# SPS_V2-5.net
KiCad netlist of a schematic drawn in EAGLE
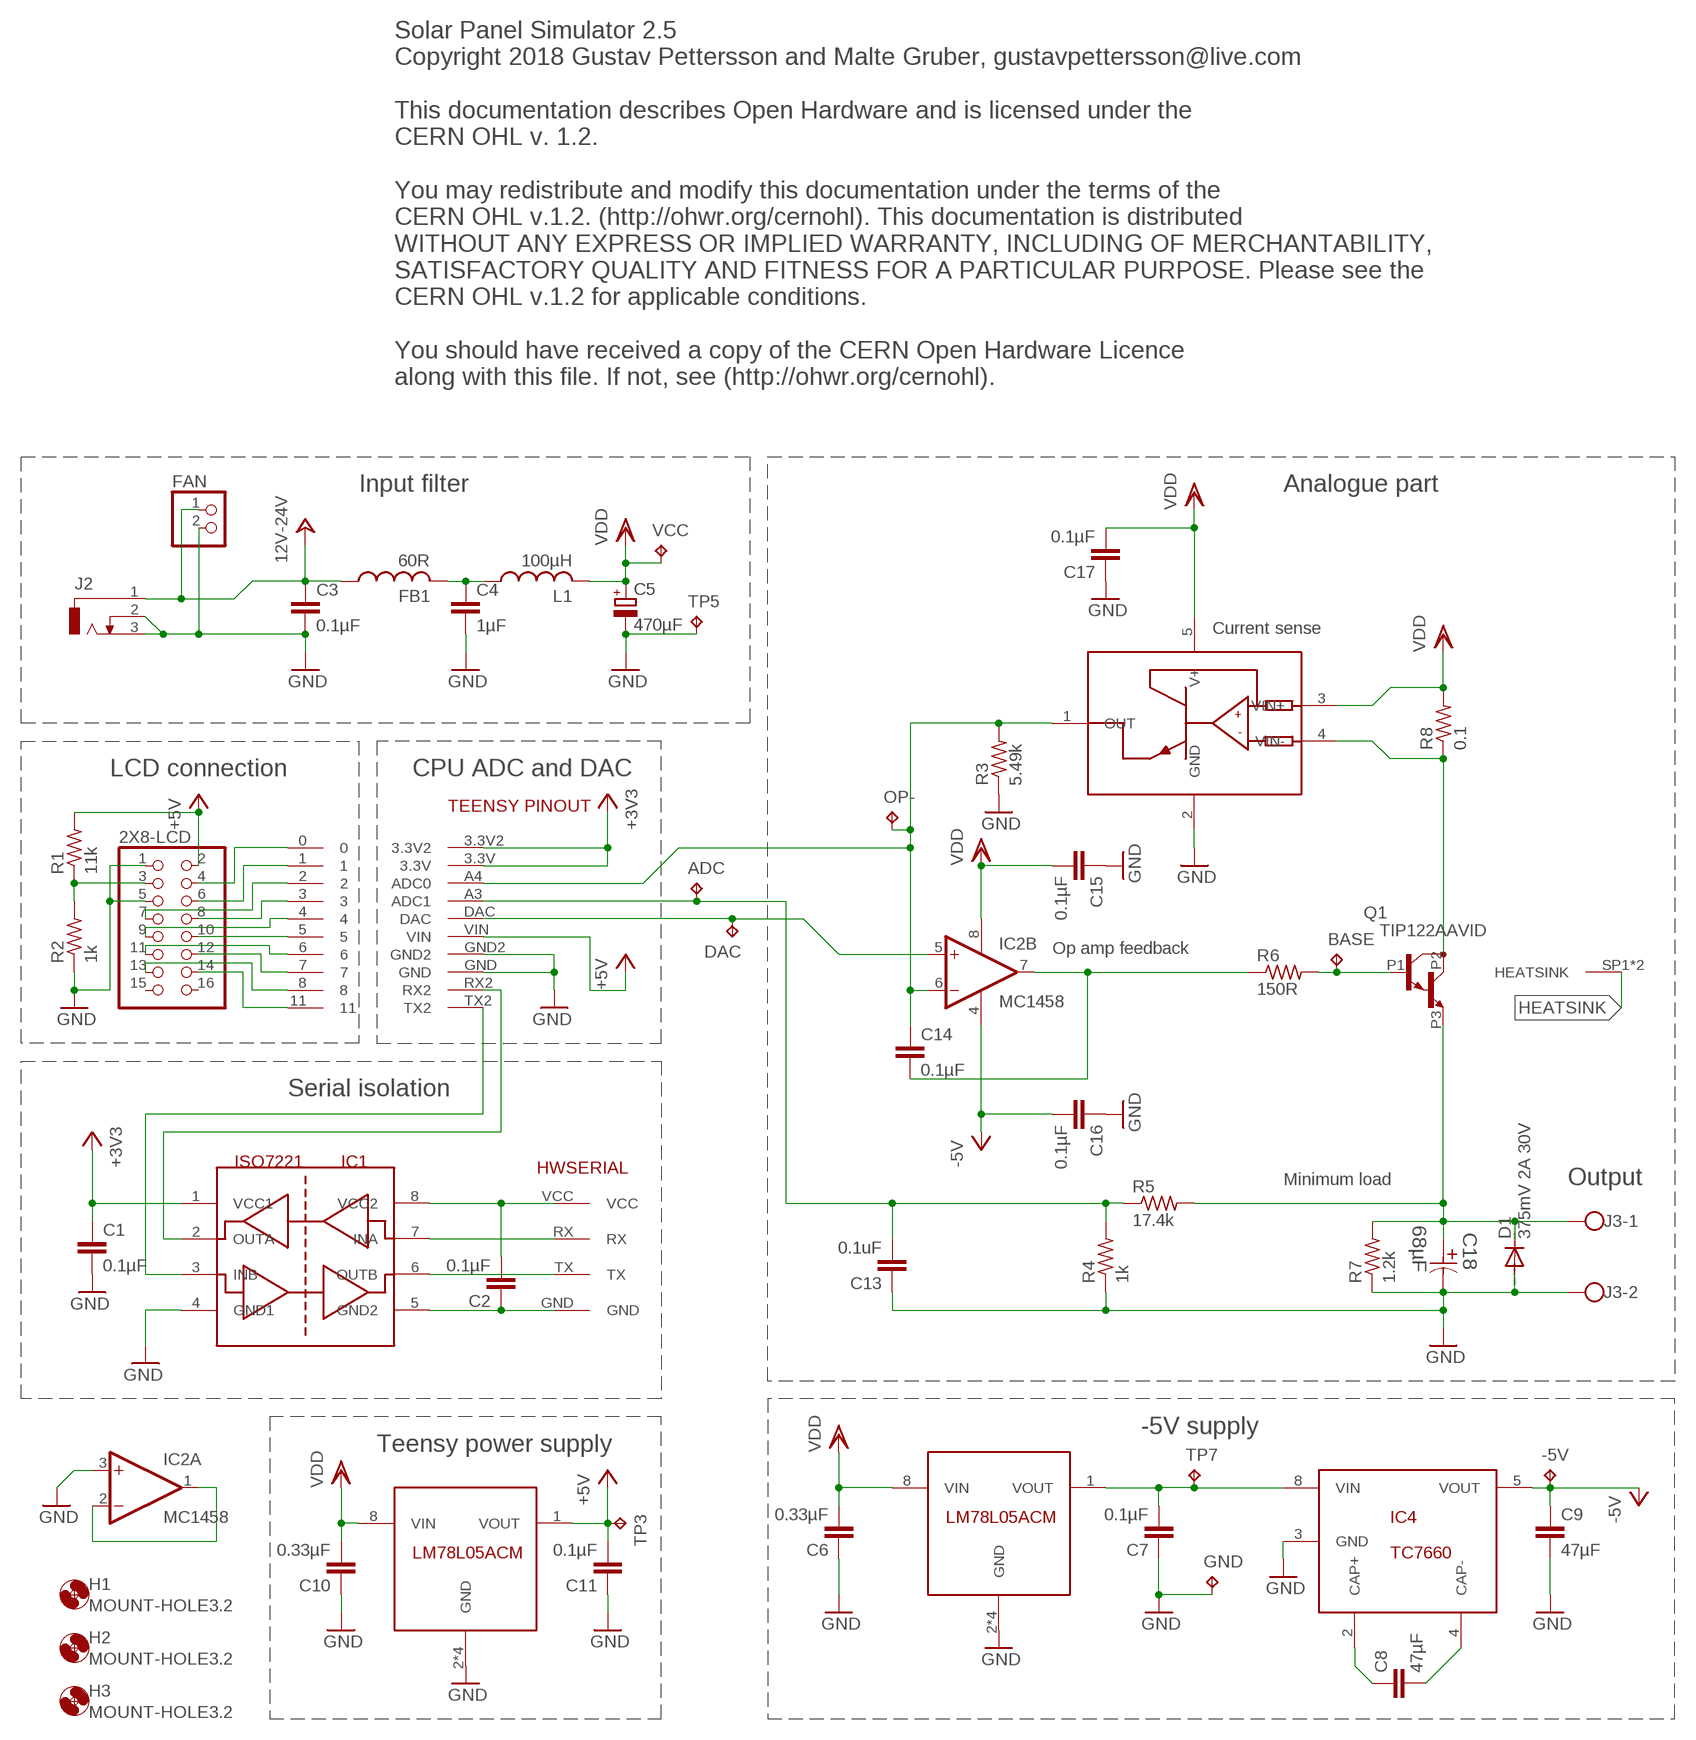
[diagram p0: schematic, sheet 1]

(export (version "E")
  (design (tool "Eeschema 10.0.6"))
  (components
    (comp (ref "-5V")
      (value "TPTP10R")
      (footprint "eagle-import:TP10R")
      (libsource (lib "eagle-import") (part "TPTP10R"))
    )
    (comp (ref "2X8-LCD")
      (value "PINHD-2X8")
      (footprint "eagle-import:2X08")
      (libsource (lib "eagle-import") (part "PINHD-2X8"))
    )
    (comp (ref "ADC")
      (value "TPTP10R")
      (footprint "eagle-import:TP10R")
      (libsource (lib "eagle-import") (part "TPTP10R"))
    )
    (comp (ref "BASE")
      (value "TPTP10R")
      (footprint "eagle-import:TP10R")
      (libsource (lib "eagle-import") (part "TPTP10R"))
    )
    (comp (ref "C1")
      (value "0.1µF")
      (footprint "eagle-import:C0603")
      (libsource (lib "eagle-import") (part "C-EUC0603"))
    )
    (comp (ref "C2")
      (value "0.1µF")
      (footprint "eagle-import:C0603")
      (libsource (lib "eagle-import") (part "C-EUC0603"))
    )
    (comp (ref "C3")
      (value "0.1µF")
      (footprint "eagle-import:C0603")
      (libsource (lib "eagle-import") (part "C-EUC0603"))
    )
    (comp (ref "C4")
      (value "1µF")
      (footprint "eagle-import:C0603")
      (libsource (lib "eagle-import") (part "C-EUC0603"))
    )
    (comp (ref "C5")
      (value "470µF")
      (footprint "eagle-import:12.5MMSMD")
      (libsource (lib "eagle-import") (part "12.5CAP"))
    )
    (comp (ref "C6")
      (value "0.33µF")
      (footprint "eagle-import:C0603")
      (libsource (lib "eagle-import") (part "C-EUC0603"))
    )
    (comp (ref "C7")
      (value "0.1µF")
      (footprint "eagle-import:C0603")
      (libsource (lib "eagle-import") (part "C-EUC0603"))
    )
    (comp (ref "C8")
      (value "47µF")
      (footprint "eagle-import:C1206")
      (libsource (lib "eagle-import") (part "resistor_C-EUC1206"))
    )
    (comp (ref "C9")
      (value "47µF")
      (footprint "eagle-import:C1206")
      (libsource (lib "eagle-import") (part "resistor_C-EUC1206"))
    )
    (comp (ref "C10")
      (value "0.33µF")
      (footprint "eagle-import:C0603")
      (libsource (lib "eagle-import") (part "C-EUC0603"))
    )
    (comp (ref "C11")
      (value "0.1µF")
      (footprint "eagle-import:C0603")
      (libsource (lib "eagle-import") (part "C-EUC0603"))
    )
    (comp (ref "C13")
      (value "0.1uF")
      (footprint "eagle-import:C0603")
      (libsource (lib "eagle-import") (part "C-EUC0603"))
    )
    (comp (ref "C14")
      (value "0.1µF")
      (footprint "eagle-import:C0603")
      (libsource (lib "eagle-import") (part "C-EUC0603"))
    )
    (comp (ref "C15")
      (value "0.1µF")
      (footprint "eagle-import:C0603")
      (libsource (lib "eagle-import") (part "C-EUC0603"))
    )
    (comp (ref "C16")
      (value "0.1µF")
      (footprint "eagle-import:C0603")
      (libsource (lib "eagle-import") (part "C-EUC0603"))
    )
    (comp (ref "C17")
      (value "0.1µF")
      (footprint "eagle-import:C0603")
      (libsource (lib "eagle-import") (part "C-EUC0603"))
    )
    (comp (ref "C18")
      (value "68µF")
      (footprint "eagle-import:CAPAE660X800N")
      (fields (field (name "MPN") "EEE-FPV680XAP") (field (name "TOLERANCE") "±20 %"))
      (libsource (lib "eagle-import") (part "EEE--CASE-D8FPV680XAP"))
    )
    (comp (ref "D1")
      (value "375mV 2A 30V")
      (footprint "eagle-import:DO214AC")
      (libsource (lib "eagle-import") (part "DIODE-DO214AC"))
    )
    (comp (ref "DAC")
      (value "TPTP10R")
      (footprint "eagle-import:TP10R")
      (libsource (lib "eagle-import") (part "TPTP10R"))
    )
    (comp (ref "DB1")
      (value "TEENSY3.2")
      (footprint "eagle-import:TEENSY3.2")
      (libsource (lib "eagle-import") (part "TEENSY3.2"))
    )
    (comp (ref "FAN")
      (value "PINHD-1X2")
      (footprint "eagle-import:1X02")
      (libsource (lib "eagle-import") (part "PINHD-1X2"))
    )
    (comp (ref "FB1")
      (value "60R")
      (footprint "eagle-import:R1206")
      (libsource (lib "eagle-import") (part "1206FERRITEBEAD"))
    )
    (comp (ref "GND")
      (value "TPTP10R")
      (footprint "eagle-import:TP10R")
      (libsource (lib "eagle-import") (part "TPTP10R"))
    )
    (comp (ref "H1")
      (value "MOUNT-HOLE3.2")
      (footprint "eagle-import:3,2")
      (libsource (lib "eagle-import") (part "MOUNT-HOLE3.2"))
    )
    (comp (ref "H2")
      (value "MOUNT-HOLE3.2")
      (footprint "eagle-import:3,2")
      (libsource (lib "eagle-import") (part "MOUNT-HOLE3.2"))
    )
    (comp (ref "H3")
      (value "MOUNT-HOLE3.2")
      (footprint "eagle-import:3,2")
      (libsource (lib "eagle-import") (part "MOUNT-HOLE3.2"))
    )
    (comp (ref "IC1")
      (value "ISO7221")
      (footprint "eagle-import:SO8")
      (libsource (lib "eagle-import") (part "ISO7221"))
    )
    (comp (ref "IC2")
      (value "MC1458")
      (footprint "eagle-import:SO08")
      (libsource (lib "eagle-import") (part "4558DLM"))
    )
    (comp (ref "IC3")
      (value "LM78L05ACM")
      (footprint "eagle-import:SO8")
      (libsource (lib "eagle-import") (part "LM78L05ACM"))
    )
    (comp (ref "IC4")
      (value "TC7660")
      (footprint "eagle-import:SO8")
      (libsource (lib "eagle-import") (part "TL7660"))
    )
    (comp (ref "IC5")
      (value "LM78L05ACM")
      (footprint "eagle-import:SO8")
      (libsource (lib "eagle-import") (part "LM78L05ACM"))
    )
    (comp (ref "IC6")
      (value "INA139")
      (footprint "eagle-import:SOT23-5L")
      (libsource (lib "eagle-import") (part "INA139"))
    )
    (comp (ref "J1")
      (value "HWSERIAL")
      (footprint "eagle-import:HWSERIAL")
      (libsource (lib "eagle-import") (part "HWSERIAL"))
    )
    (comp (ref "J2")
      (value "DCJ0303")
      (footprint "eagle-import:DCJ0303")
      (libsource (lib "eagle-import") (part "DCJ0303"))
    )
    (comp (ref "J3")
      (value "W237-102")
      (footprint "eagle-import:W237-102")
      (fields (field (name "MPN") "237-102"))
      (libsource (lib "eagle-import") (part "W237-102"))
    )
    (comp (ref "L1")
      (value "100µH")
      (footprint "eagle-import:1210INDUCTOR")
      (libsource (lib "eagle-import") (part "1210INDUCTOR"))
    )
    (comp (ref "OP-")
      (value "TPTP10R")
      (footprint "eagle-import:TP10R")
      (libsource (lib "eagle-import") (part "TPTP10R"))
    )
    (comp (ref "Q1")
      (value "TIP122AAVID")
      (footprint "eagle-import:OP-220-AAVID")
      (libsource (lib "eagle-import") (part "TIP122AAVID"))
    )
    (comp (ref "R1")
      (value "11k")
      (footprint "eagle-import:R0603")
      (libsource (lib "eagle-import") (part "R-US_R0603"))
    )
    (comp (ref "R2")
      (value "1k")
      (footprint "eagle-import:R0603")
      (libsource (lib "eagle-import") (part "R-US_R0603"))
    )
    (comp (ref "R3")
      (value "5.49k")
      (footprint "eagle-import:R0603")
      (libsource (lib "eagle-import") (part "R-US_R0603"))
    )
    (comp (ref "R4")
      (value "1k")
      (footprint "eagle-import:R0603")
      (libsource (lib "eagle-import") (part "R-US_R0603"))
    )
    (comp (ref "R5")
      (value "17.4k")
      (footprint "eagle-import:R0603")
      (libsource (lib "eagle-import") (part "R-US_R0603"))
    )
    (comp (ref "R6")
      (value "150R")
      (footprint "eagle-import:R0603")
      (libsource (lib "eagle-import") (part "R-US_R0603"))
    )
    (comp (ref "R7")
      (value "1.2k")
      (footprint "eagle-import:R1206")
      (libsource (lib "eagle-import") (part "R-US_R1206"))
    )
    (comp (ref "R8")
      (value "0.1")
      (footprint "eagle-import:R1206")
      (libsource (lib "eagle-import") (part "R-US_R1206"))
    )
    (comp (ref "TP3")
      (value "TPTP10R")
      (footprint "eagle-import:TP10R")
      (libsource (lib "eagle-import") (part "TPTP10R"))
    )
    (comp (ref "TP5")
      (value "TPTP10R")
      (footprint "eagle-import:TP10R")
      (libsource (lib "eagle-import") (part "TPTP10R"))
    )
    (comp (ref "TP7")
      (value "TPTP10R")
      (footprint "eagle-import:TP10R")
      (libsource (lib "eagle-import") (part "TPTP10R"))
    )
    (comp (ref "VCC")
      (value "TPTP10R")
      (footprint "eagle-import:TP10R")
      (libsource (lib "eagle-import") (part "TPTP10R"))
    )
  )
  (nets
    (net (code "1") (name "+3V3") (class "Default")
      (node (ref "C1") (pin "1") (pinfunction "1_1") (pintype "passive"))
      (node (ref "DB1") (pin "3.3V") (pinfunction "3.3V_3.3V") (pintype "bidirectional"))
      (node (ref "DB1") (pin "3.3V2") (pinfunction "3.3V2_3.3V2") (pintype "bidirectional"))
      (node (ref "IC1") (pin "1") (pinfunction "VCC1_1") (pintype "bidirectional"))
    )
    (net (code "2") (name "+5V") (class "Default")
      (node (ref "2X8-LCD") (pin "2") (pinfunction "2_2") (pintype "passive"))
      (node (ref "C11") (pin "2") (pinfunction "2_2") (pintype "passive"))
      (node (ref "DB1") (pin "VIN") (pinfunction "VIN_VIN") (pintype "bidirectional"))
      (node (ref "IC5") (pin "1") (pinfunction "VOUT_1") (pintype "bidirectional"))
      (node (ref "R1") (pin "2") (pinfunction "2_2") (pintype "passive"))
      (node (ref "TP3") (pin "TP") (pinfunction "TP_TP") (pintype "input"))
    )
    (net (code "3") (name "-5V") (class "Default")
      (node (ref "-5V") (pin "TP") (pinfunction "TP_TP") (pintype "input"))
      (node (ref "C16") (pin "2") (pinfunction "2_2") (pintype "passive"))
      (node (ref "C9") (pin "1") (pinfunction "1_1") (pintype "passive"))
      (node (ref "IC2") (pin "4") (pinfunction "V-_4") (pintype "power_in"))
      (node (ref "IC4") (pin "5") (pinfunction "VOUT_5") (pintype "bidirectional"))
    )
    (net (code "4") (name "12V-24V") (class "Default")
      (node (ref "C3") (pin "1") (pinfunction "1_1") (pintype "passive"))
      (node (ref "FAN") (pin "1") (pinfunction "1_1") (pintype "passive"))
      (node (ref "FB1") (pin "1") (pinfunction "1_1") (pintype "passive"))
      (node (ref "J2") (pin "1") (pinfunction "1_1") (pintype "passive"))
    )
    (net (code "5") (name "GND") (class "Default")
      (node (ref "2X8-LCD") (pin "1") (pinfunction "1_1") (pintype "passive"))
      (node (ref "2X8-LCD") (pin "5") (pinfunction "5_5") (pintype "passive"))
      (node (ref "C1") (pin "2") (pinfunction "2_2") (pintype "passive"))
      (node (ref "C10") (pin "1") (pinfunction "1_1") (pintype "passive"))
      (node (ref "C11") (pin "1") (pinfunction "1_1") (pintype "passive"))
      (node (ref "C13") (pin "1") (pinfunction "1_1") (pintype "passive"))
      (node (ref "C15") (pin "1") (pinfunction "1_1") (pintype "passive"))
      (node (ref "C16") (pin "1") (pinfunction "1_1") (pintype "passive"))
      (node (ref "C17") (pin "1") (pinfunction "1_1") (pintype "passive"))
      (node (ref "C18") (pin "2") (pinfunction "2_2") (pintype "passive"))
      (node (ref "C3") (pin "2") (pinfunction "2_2") (pintype "passive"))
      (node (ref "C4") (pin "2") (pinfunction "2_2") (pintype "passive"))
      (node (ref "C5") (pin "P$1") (pinfunction "-_P$1") (pintype "passive"))
      (node (ref "C6") (pin "1") (pinfunction "1_1") (pintype "passive"))
      (node (ref "C7") (pin "1") (pinfunction "1_1") (pintype "passive"))
      (node (ref "C9") (pin "2") (pinfunction "2_2") (pintype "passive"))
      (node (ref "D1") (pin "A") (pinfunction "A_A") (pintype "passive"))
      (node (ref "DB1") (pin "GND") (pinfunction "GND_GND") (pintype "bidirectional"))
      (node (ref "DB1") (pin "GND2") (pinfunction "GND2_GND2") (pintype "bidirectional"))
      (node (ref "FAN") (pin "2") (pinfunction "2_2") (pintype "passive"))
      (node (ref "GND") (pin "TP") (pinfunction "TP_TP") (pintype "input"))
      (node (ref "IC1") (pin "4") (pinfunction "GND1_4") (pintype "bidirectional"))
      (node (ref "IC2") (pin "3") (pinfunction "+IN_3") (pintype "input"))
      (node (ref "IC3") (pin "2") (pinfunction "GND_2") (pintype "bidirectional"))
      (node (ref "IC3") (pin "3") (pinfunction "GND_3") (pintype "bidirectional"))
      (node (ref "IC3") (pin "6") (pinfunction "GND_6") (pintype "bidirectional"))
      (node (ref "IC3") (pin "7") (pinfunction "GND_7") (pintype "bidirectional"))
      (node (ref "IC4") (pin "3") (pinfunction "GND_3") (pintype "bidirectional"))
      (node (ref "IC5") (pin "2") (pinfunction "GND_2") (pintype "bidirectional"))
      (node (ref "IC5") (pin "3") (pinfunction "GND_3") (pintype "bidirectional"))
      (node (ref "IC5") (pin "6") (pinfunction "GND_6") (pintype "bidirectional"))
      (node (ref "IC5") (pin "7") (pinfunction "GND_7") (pintype "bidirectional"))
      (node (ref "IC6") (pin "2") (pinfunction "GND_2") (pintype "bidirectional"))
      (node (ref "J2") (pin "2") (pinfunction "2_2") (pintype "passive"))
      (node (ref "J2") (pin "3") (pinfunction "3_3") (pintype "passive"))
      (node (ref "J3") (pin "2") (pinfunction "KL_2") (pintype "passive"))
      (node (ref "R2") (pin "1") (pinfunction "1_1") (pintype "passive"))
      (node (ref "R3") (pin "1") (pinfunction "1_1") (pintype "passive"))
      (node (ref "R4") (pin "1") (pinfunction "1_1") (pintype "passive"))
      (node (ref "R7") (pin "1") (pinfunction "1_1") (pintype "passive"))
      (node (ref "TP5") (pin "TP") (pinfunction "TP_TP") (pintype "input"))
    )
    (net (code "6") (name "HEATSINK") (class "Default")
      (node (ref "Q1") (pin "SP1") (pinfunction "HEATSINK_SP1") (pintype "bidirectional"))
      (node (ref "Q1") (pin "SP2") (pinfunction "HEATSINK_SP2") (pintype "bidirectional"))
    )
    (net (code "7") (name "Net-(2X8-LCD-Pad3)") (class "Default")
      (node (ref "2X8-LCD") (pin "3") (pinfunction "3_3") (pintype "passive"))
      (node (ref "R1") (pin "1") (pinfunction "1_1") (pintype "passive"))
      (node (ref "R2") (pin "2") (pinfunction "2_2") (pintype "passive"))
    )
    (net (code "8") (name "Net-(2X8-LCD-Pad4)") (class "Default")
      (node (ref "2X8-LCD") (pin "4") (pinfunction "4_4") (pintype "passive"))
      (node (ref "DB1") (pin "0") (pinfunction "0_0") (pintype "bidirectional"))
    )
    (net (code "9") (name "Net-(2X8-LCD-Pad6)") (class "Default")
      (node (ref "2X8-LCD") (pin "6") (pinfunction "6_6") (pintype "passive"))
      (node (ref "DB1") (pin "1") (pinfunction "1_1") (pintype "bidirectional"))
    )
    (net (code "10") (name "Net-(2X8-LCD-Pad7)") (class "Default")
      (node (ref "2X8-LCD") (pin "7") (pinfunction "7_7") (pintype "passive"))
      (node (ref "DB1") (pin "2") (pinfunction "2_2") (pintype "bidirectional"))
    )
    (net (code "11") (name "Net-(2X8-LCD-Pad8)") (class "Default")
      (node (ref "2X8-LCD") (pin "8") (pinfunction "8_8") (pintype "passive"))
      (node (ref "DB1") (pin "3") (pinfunction "3_3") (pintype "bidirectional"))
    )
    (net (code "12") (name "Net-(2X8-LCD-Pad9)") (class "Default")
      (node (ref "2X8-LCD") (pin "9") (pinfunction "9_9") (pintype "passive"))
      (node (ref "DB1") (pin "4") (pinfunction "4_4") (pintype "bidirectional"))
    )
    (net (code "13") (name "Net-(2X8-LCD-Pad10)") (class "Default")
      (node (ref "2X8-LCD") (pin "10") (pinfunction "10_10") (pintype "passive"))
      (node (ref "DB1") (pin "5") (pinfunction "5_5") (pintype "bidirectional"))
    )
    (net (code "14") (name "Net-(2X8-LCD-Pad11)") (class "Default")
      (node (ref "2X8-LCD") (pin "11") (pinfunction "11_11") (pintype "passive"))
      (node (ref "DB1") (pin "6") (pinfunction "6_6") (pintype "bidirectional"))
    )
    (net (code "15") (name "Net-(2X8-LCD-Pad12)") (class "Default")
      (node (ref "2X8-LCD") (pin "12") (pinfunction "12_12") (pintype "passive"))
      (node (ref "DB1") (pin "7") (pinfunction "7_7") (pintype "bidirectional"))
    )
    (net (code "16") (name "Net-(2X8-LCD-Pad13)") (class "Default")
      (node (ref "2X8-LCD") (pin "13") (pinfunction "13_13") (pintype "passive"))
      (node (ref "DB1") (pin "8") (pinfunction "8_8") (pintype "bidirectional"))
    )
    (net (code "17") (name "Net-(2X8-LCD-Pad14)") (class "Default")
      (node (ref "2X8-LCD") (pin "14") (pinfunction "14_14") (pintype "passive"))
      (node (ref "DB1") (pin "11") (pinfunction "11_11") (pintype "bidirectional"))
    )
    (net (code "18") (name "Net-(DB1-ADC0)") (class "Default")
      (node (ref "C14") (pin "1") (pinfunction "1_1") (pintype "passive"))
      (node (ref "DB1") (pin "A4") (pinfunction "ADC0_A4") (pintype "bidirectional"))
      (node (ref "IC2") (pin "6") (pinfunction "-IN_6") (pintype "input"))
      (node (ref "IC6") (pin "1") (pinfunction "OUT_1") (pintype "bidirectional"))
      (node (ref "OP-") (pin "TP") (pinfunction "TP_TP") (pintype "input"))
      (node (ref "R3") (pin "2") (pinfunction "2_2") (pintype "passive"))
    )
    (net (code "19") (name "Net-(DB1-ADC1)") (class "Default")
      (node (ref "ADC") (pin "TP") (pinfunction "TP_TP") (pintype "input"))
      (node (ref "C13") (pin "2") (pinfunction "2_2") (pintype "passive"))
      (node (ref "DB1") (pin "A3") (pinfunction "ADC1_A3") (pintype "bidirectional"))
      (node (ref "R4") (pin "2") (pinfunction "2_2") (pintype "passive"))
      (node (ref "R5") (pin "1") (pinfunction "1_1") (pintype "passive"))
    )
    (net (code "20") (name "Net-(IC1-GND2)") (class "Default")
      (node (ref "C2") (pin "1") (pinfunction "1_1") (pintype "passive"))
      (node (ref "IC1") (pin "5") (pinfunction "GND2_5") (pintype "bidirectional"))
      (node (ref "J1") (pin "GND") (pinfunction "GND_GND") (pintype "bidirectional"))
    )
    (net (code "21") (name "Net-(IC1-INA)") (class "Default")
      (node (ref "IC1") (pin "7") (pinfunction "INA_7") (pintype "bidirectional"))
      (node (ref "J1") (pin "RX") (pinfunction "RX_RX") (pintype "bidirectional"))
    )
    (net (code "22") (name "Net-(IC1-INB)") (class "Default")
      (node (ref "DB1") (pin "TX2") (pinfunction "TX2_TX2") (pintype "bidirectional"))
      (node (ref "IC1") (pin "3") (pinfunction "INB_3") (pintype "bidirectional"))
    )
    (net (code "23") (name "Net-(IC1-OUTA)") (class "Default")
      (node (ref "DB1") (pin "RX2") (pinfunction "RX2_RX2") (pintype "bidirectional"))
      (node (ref "IC1") (pin "2") (pinfunction "OUTA_2") (pintype "bidirectional"))
    )
    (net (code "24") (name "Net-(IC1-OUTB)") (class "Default")
      (node (ref "IC1") (pin "6") (pinfunction "OUTB_6") (pintype "bidirectional"))
      (node (ref "J1") (pin "TX") (pinfunction "TX_TX") (pintype "bidirectional"))
    )
    (net (code "25") (name "Net-(IC1-VCC2)") (class "Default")
      (node (ref "C2") (pin "2") (pinfunction "2_2") (pintype "passive"))
      (node (ref "IC1") (pin "8") (pinfunction "VCC2_8") (pintype "bidirectional"))
      (node (ref "J1") (pin "VCC") (pinfunction "VCC_VCC") (pintype "bidirectional"))
    )
    (net (code "26") (name "Net-(IC2A--IN)") (class "Default")
      (node (ref "IC2") (pin "1") (pinfunction "OUT_1") (pintype "output"))
      (node (ref "IC2") (pin "2") (pinfunction "-IN_2") (pintype "input"))
    )
    (net (code "27") (name "Net-(IC2B-+IN)") (class "Default")
      (node (ref "DAC") (pin "TP") (pinfunction "TP_TP") (pintype "input"))
      (node (ref "DB1") (pin "DAC") (pinfunction "DAC_DAC") (pintype "bidirectional"))
      (node (ref "IC2") (pin "5") (pinfunction "+IN_5") (pintype "input"))
    )
    (net (code "28") (name "Net-(IC2B-OUT)") (class "Default")
      (node (ref "C14") (pin "2") (pinfunction "2_2") (pintype "passive"))
      (node (ref "IC2") (pin "7") (pinfunction "OUT_7") (pintype "output"))
      (node (ref "R6") (pin "1") (pinfunction "1_1") (pintype "passive"))
    )
    (net (code "29") (name "Net-(IC3-VOUT)") (class "Default")
      (node (ref "C7") (pin "2") (pinfunction "2_2") (pintype "passive"))
      (node (ref "IC3") (pin "1") (pinfunction "VOUT_1") (pintype "bidirectional"))
      (node (ref "IC4") (pin "8") (pinfunction "VIN_8") (pintype "bidirectional"))
      (node (ref "TP7") (pin "TP") (pinfunction "TP_TP") (pintype "input"))
    )
    (net (code "30") (name "Net-(IC4-CAP+)") (class "Default")
      (node (ref "C8") (pin "1") (pinfunction "1_1") (pintype "passive"))
      (node (ref "IC4") (pin "2") (pinfunction "CAP+_2") (pintype "bidirectional"))
    )
    (net (code "31") (name "Net-(IC4-CAP-)") (class "Default")
      (node (ref "C8") (pin "2") (pinfunction "2_2") (pintype "passive"))
      (node (ref "IC4") (pin "4") (pinfunction "CAP-_4") (pintype "bidirectional"))
    )
    (net (code "32") (name "Net-(IC6-VIN-)") (class "Default")
      (node (ref "IC6") (pin "4") (pinfunction "VIN-_4") (pintype "bidirectional"))
      (node (ref "Q1") (pin "P2") (pinfunction "C_P2") (pintype "passive"))
      (node (ref "R8") (pin "1") (pinfunction "1_1") (pintype "passive"))
    )
    (net (code "33") (name "Net-(J3A-KL)") (class "Default")
      (node (ref "C18") (pin "1") (pinfunction "1_1") (pintype "passive"))
      (node (ref "D1") (pin "C") (pinfunction "C_C") (pintype "passive"))
      (node (ref "J3") (pin "1") (pinfunction "KL_1") (pintype "passive"))
      (node (ref "Q1") (pin "P3") (pinfunction "E_P3") (pintype "passive"))
      (node (ref "R5") (pin "2") (pinfunction "2_2") (pintype "passive"))
      (node (ref "R7") (pin "2") (pinfunction "2_2") (pintype "passive"))
    )
    (net (code "34") (name "Net-(L1-1)") (class "Default")
      (node (ref "C4") (pin "1") (pinfunction "1_1") (pintype "passive"))
      (node (ref "FB1") (pin "2") (pinfunction "2_2") (pintype "passive"))
      (node (ref "L1") (pin "P$1") (pinfunction "1_P$1") (pintype "passive"))
    )
    (net (code "35") (name "Net-(Q1-B)") (class "Default")
      (node (ref "BASE") (pin "TP") (pinfunction "TP_TP") (pintype "input"))
      (node (ref "Q1") (pin "P1") (pinfunction "B_P1") (pintype "passive"))
      (node (ref "R6") (pin "2") (pinfunction "2_2") (pintype "passive"))
    )
    (net (code "36") (name "VDD") (class "Default")
      (node (ref "C10") (pin "2") (pinfunction "2_2") (pintype "passive"))
      (node (ref "C15") (pin "2") (pinfunction "2_2") (pintype "passive"))
      (node (ref "C17") (pin "2") (pinfunction "2_2") (pintype "passive"))
      (node (ref "C5") (pin "P$2") (pinfunction "+_P$2") (pintype "passive"))
      (node (ref "C6") (pin "2") (pinfunction "2_2") (pintype "passive"))
      (node (ref "IC2") (pin "8") (pinfunction "V+_8") (pintype "power_in"))
      (node (ref "IC3") (pin "8") (pinfunction "VIN_8") (pintype "bidirectional"))
      (node (ref "IC5") (pin "8") (pinfunction "VIN_8") (pintype "bidirectional"))
      (node (ref "IC6") (pin "3") (pinfunction "VIN+_3") (pintype "bidirectional"))
      (node (ref "IC6") (pin "5") (pinfunction "V+_5") (pintype "bidirectional"))
      (node (ref "L1") (pin "P$2") (pinfunction "2_P$2") (pintype "passive"))
      (node (ref "R8") (pin "2") (pinfunction "2_2") (pintype "passive"))
      (node (ref "VCC") (pin "TP") (pinfunction "TP_TP") (pintype "input"))
    )
    (net (code "37") (name "unconnected-(2X8-LCD-Pad15)") (class "Default")
      (node (ref "2X8-LCD") (pin "15") (pinfunction "15_15") (pintype "passive"))
    )
    (net (code "38") (name "unconnected-(2X8-LCD-Pad16)") (class "Default")
      (node (ref "2X8-LCD") (pin "16") (pinfunction "16_16") (pintype "passive"))
    )
  )
)
